# Aux_Board_V7_0.net
KiCad netlist of a schematic drawn in EAGLE
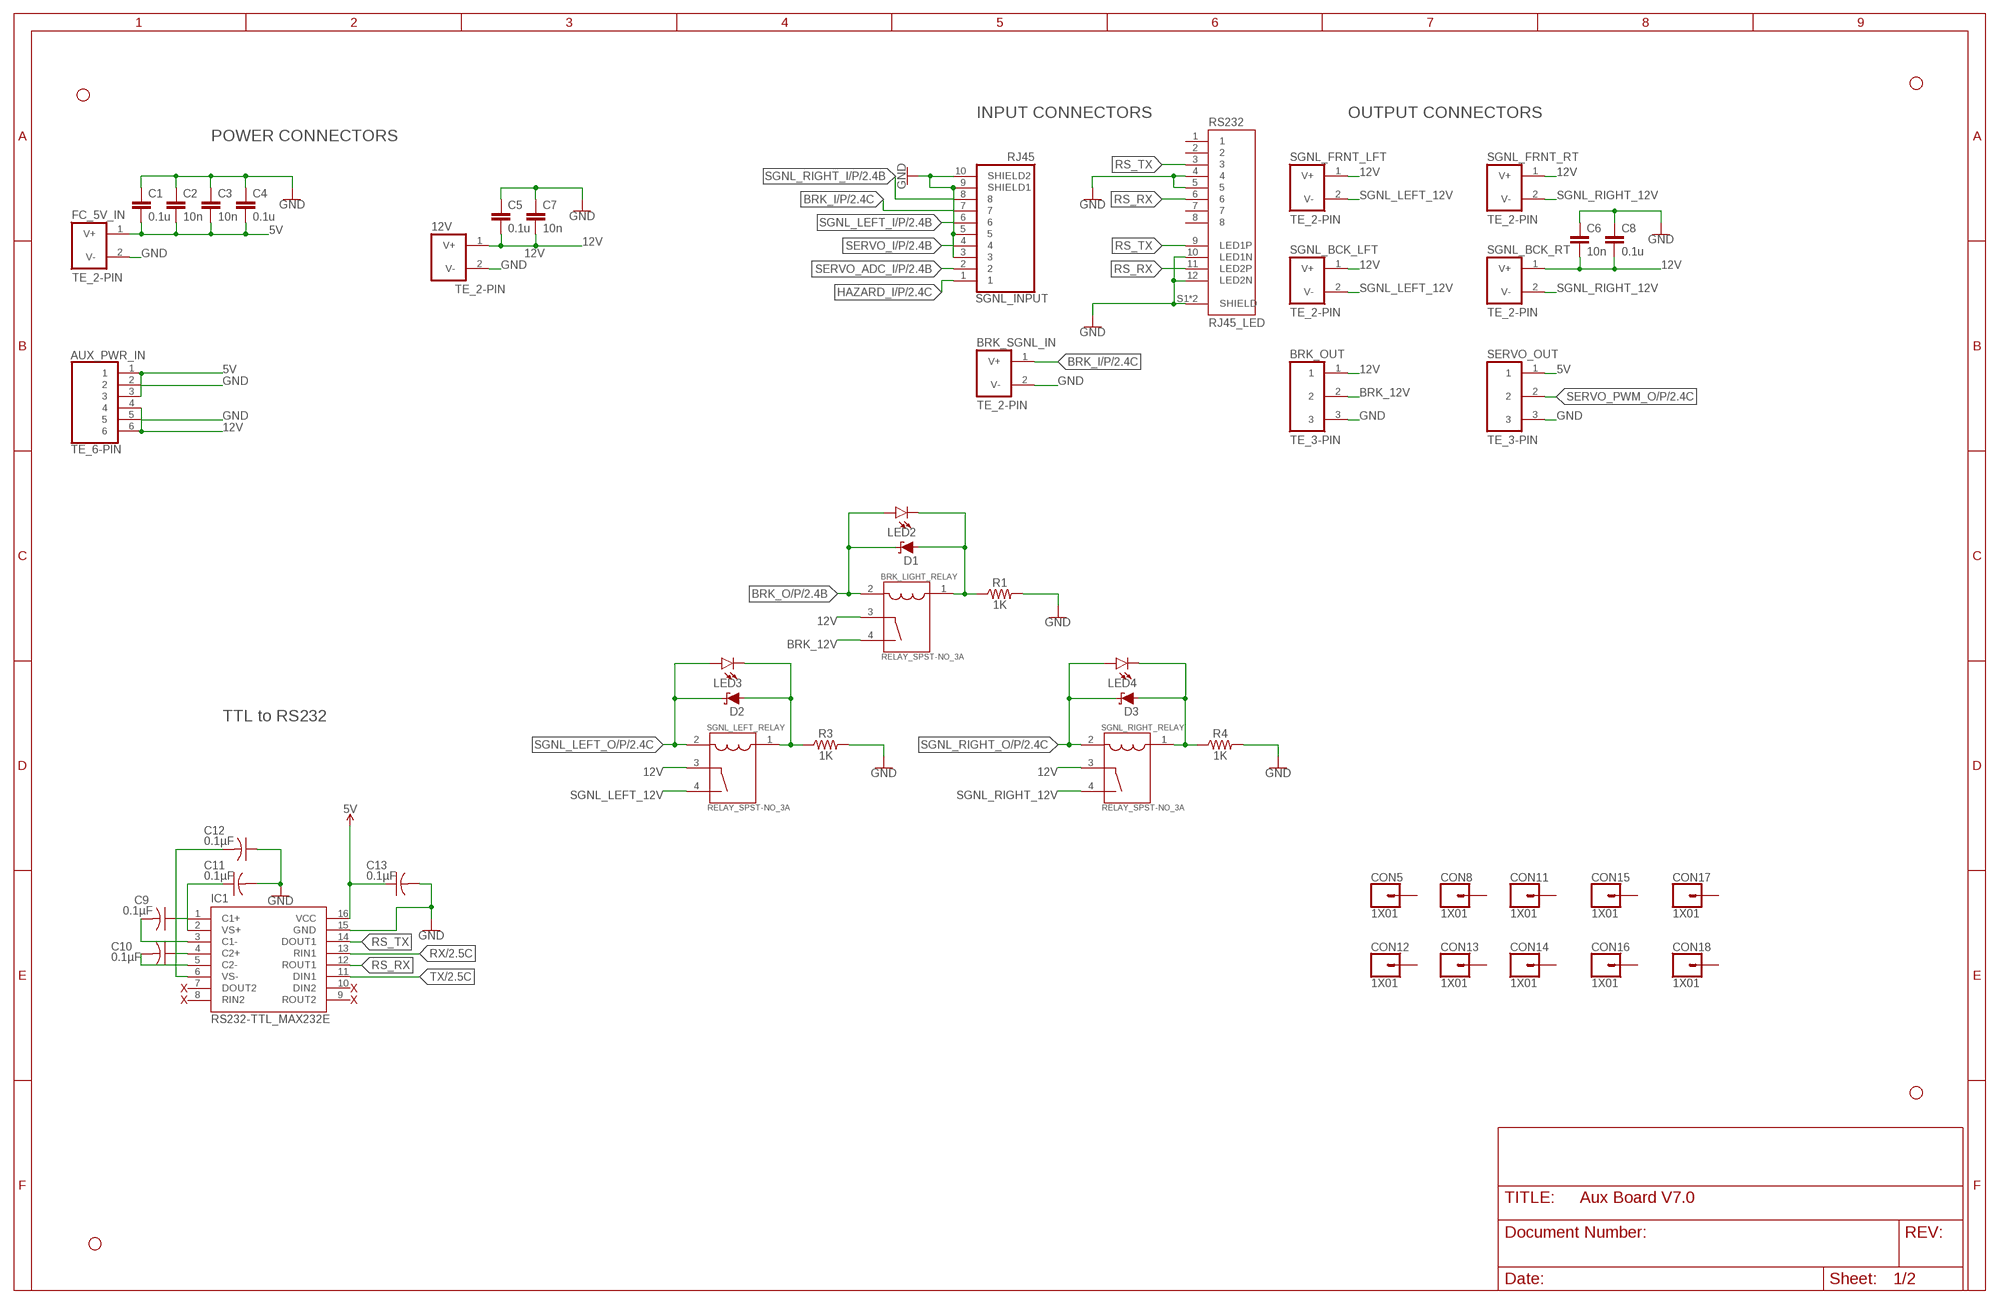
[diagram p0: schematic, sheet 1]
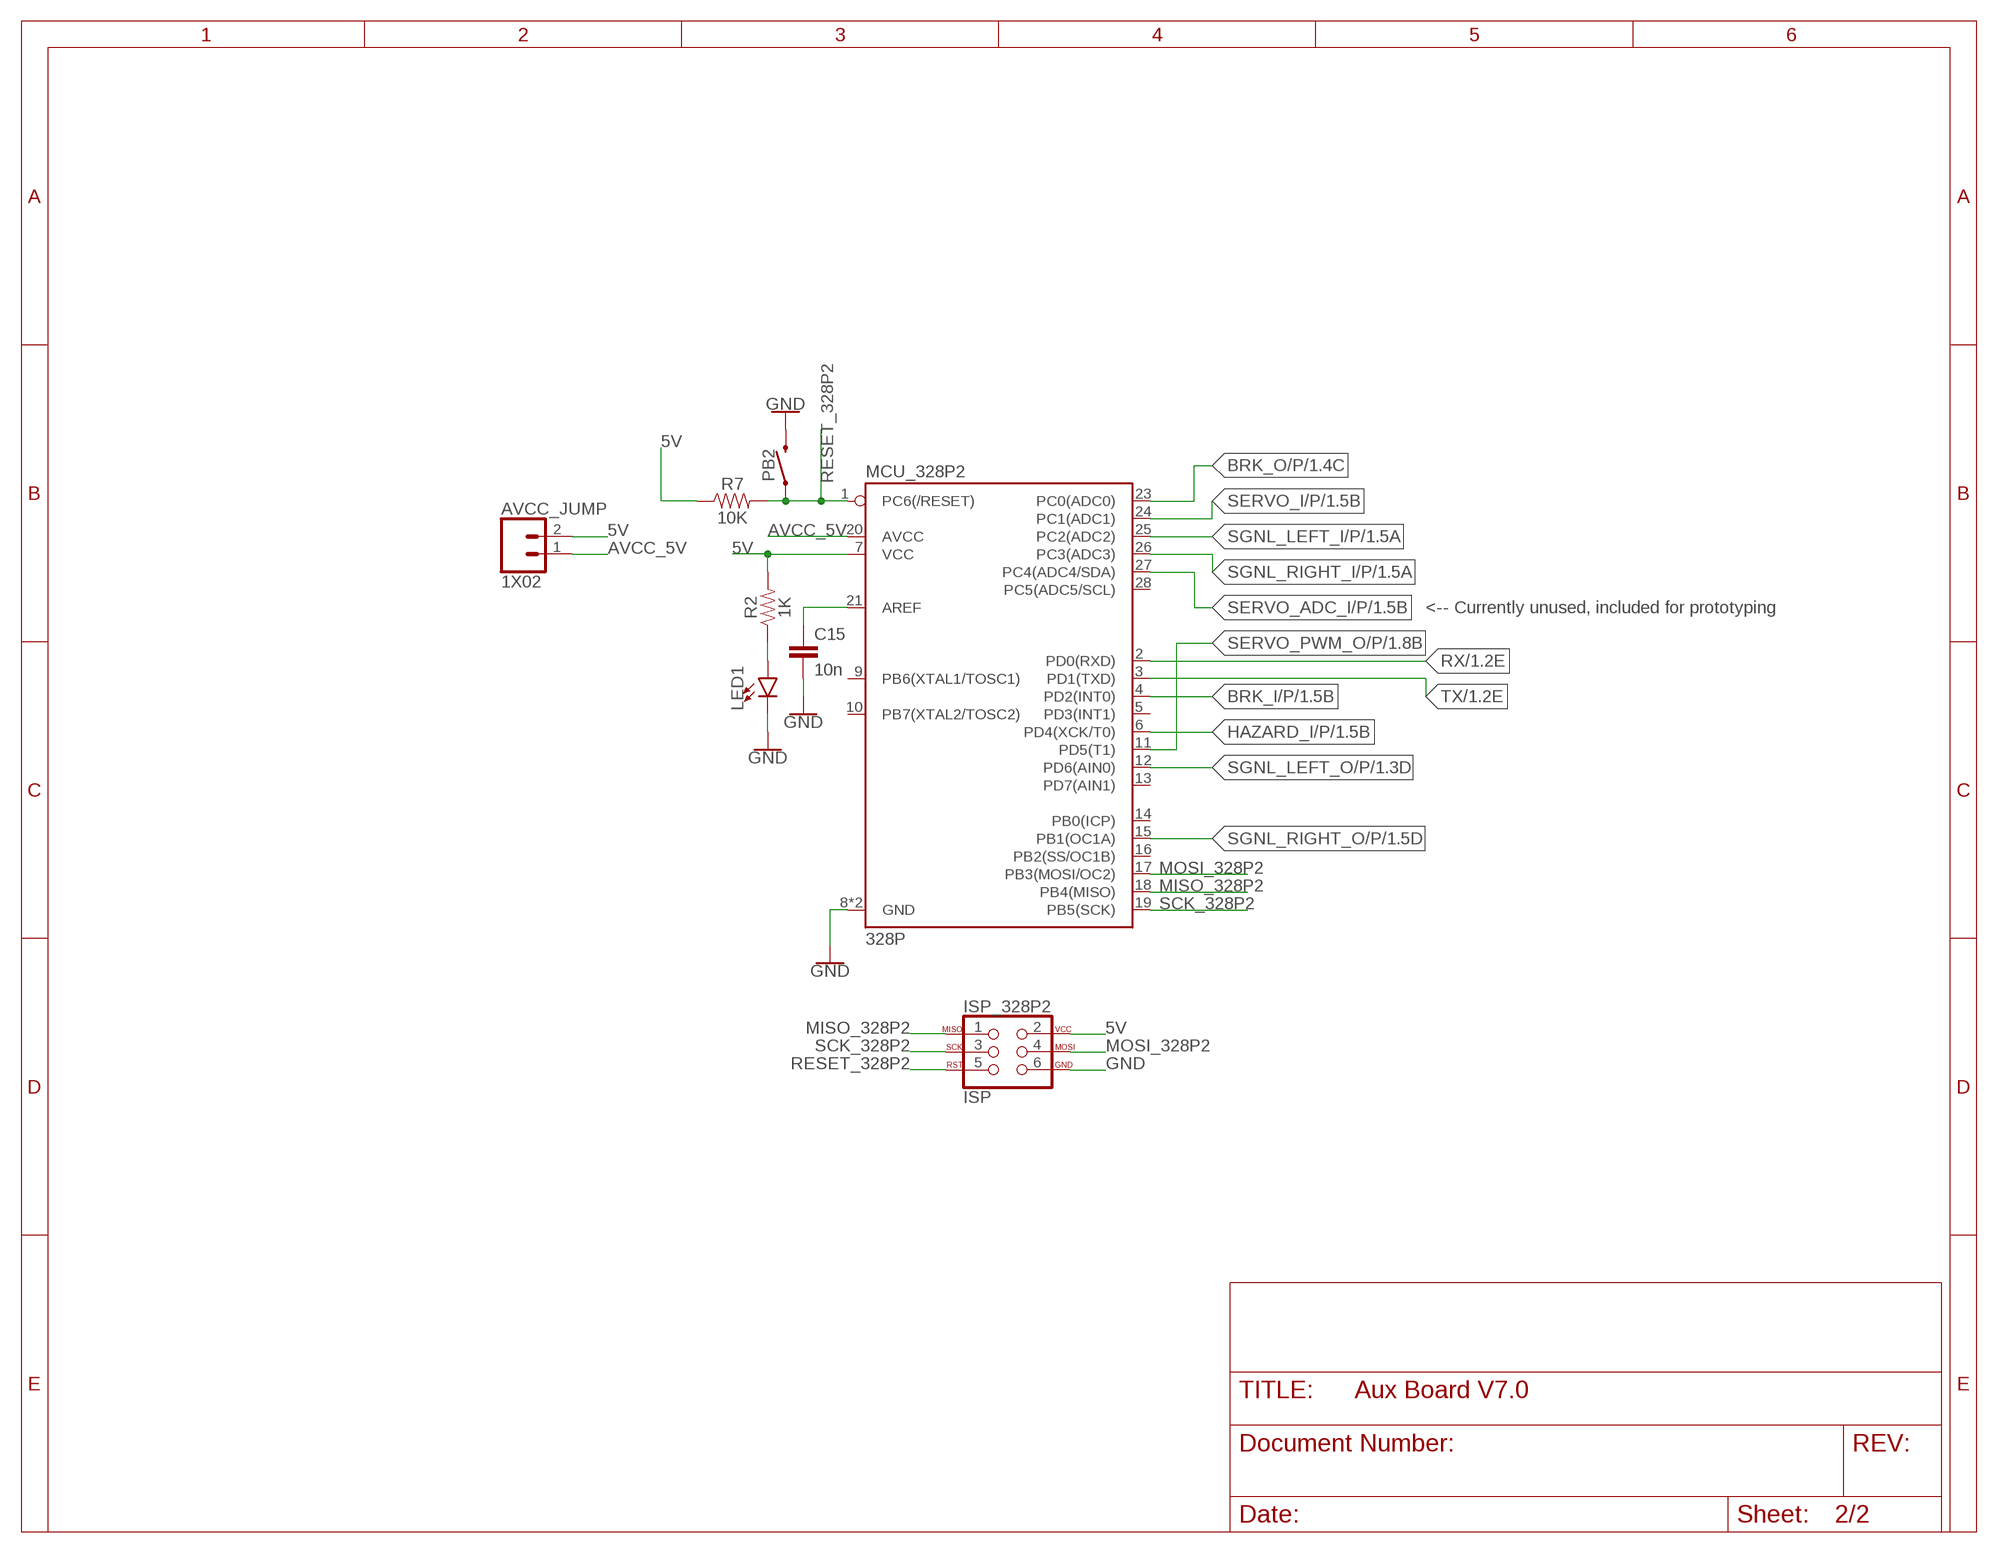
[diagram p1: schematic, sheet 2]

(export (version "E")
  (design (tool "Eeschema 10.0.6"))
  (components
    (comp (ref "AVCC_JUMP")
      (value "1X02")
      (footprint "eagle-import:1X02")
      (libsource (lib "eagle-import") (part "1X02"))
    )
    (comp (ref "C15")
      (value "10n")
      (footprint "eagle-import:0805")
      (libsource (lib "eagle-import") (part "CAPACITOR_0805"))
    )
    (comp (ref "ISP_328P2")
      (value "ISP")
      (footprint "eagle-import:ISP_CONNECTOR")
      (libsource (lib "eagle-import") (part "ISP"))
    )
    (comp (ref "LED1")
      (value "LED_0805")
      (footprint "eagle-import:0805_LED")
      (libsource (lib "eagle-import") (part "LED_0805"))
    )
    (comp (ref "MCU_328P2")
      (value "328P")
      (footprint "eagle-import:DIP28")
      (libsource (lib "eagle-import") (part "ATMEGA328P_DIP28"))
    )
    (comp (ref "PB2")
      (value "PUSHBUTTON")
      (footprint "eagle-import:PUSHBUTTON")
      (libsource (lib "eagle-import") (part "PUSHBUTTON"))
    )
    (comp (ref "R2")
      (value "1K")
      (footprint "eagle-import:0805")
      (libsource (lib "eagle-import") (part "RESISTOR_0805"))
    )
    (comp (ref "R7")
      (value "10K")
      (footprint "eagle-import:0805")
      (libsource (lib "eagle-import") (part "RESISTOR_0805"))
    )
    (comp (ref "12V")
      (value "TE_2-PIN")
      (footprint "eagle-import:TE_2-PIN")
      (libsource (lib "eagle-import") (part "TE_2-PIN"))
    )
    (comp (ref "AUX_PWR_IN")
      (value "TE_6-PIN")
      (footprint "eagle-import:TE_6-PIN")
      (libsource (lib "eagle-import") (part "TE_6-PIN"))
    )
    (comp (ref "BRK_LIGHT_RELAY")
      (value "RELAY_SPST-NO_3A")
      (footprint "eagle-import:TE_1-1721081-2")
      (fields (field (name "COMMENT") "1-1721081-2") (field (name "MF") "TE Connectivity"))
      (libsource (lib "eagle-import") (part "RELAY_SPST-NO_3A"))
    )
    (comp (ref "BRK_OUT")
      (value "TE_3-PIN")
      (footprint "eagle-import:TE_3-PIN")
      (libsource (lib "eagle-import") (part "TE_3-PIN"))
    )
    (comp (ref "BRK_SGNL_IN")
      (value "TE_2-PIN")
      (footprint "eagle-import:TE_2-PIN")
      (libsource (lib "eagle-import") (part "TE_2-PIN"))
    )
    (comp (ref "C1")
      (value "0.1u")
      (footprint "eagle-import:0805")
      (libsource (lib "eagle-import") (part "CAPACITOR_0805"))
    )
    (comp (ref "C2")
      (value "10n")
      (footprint "eagle-import:0805")
      (libsource (lib "eagle-import") (part "CAPACITOR_0805"))
    )
    (comp (ref "C3")
      (value "10n")
      (footprint "eagle-import:0805")
      (libsource (lib "eagle-import") (part "CAPACITOR_0805"))
    )
    (comp (ref "C4")
      (value "0.1u")
      (footprint "eagle-import:0805")
      (libsource (lib "eagle-import") (part "CAPACITOR_0805"))
    )
    (comp (ref "C5")
      (value "0.1u")
      (footprint "eagle-import:0805")
      (libsource (lib "eagle-import") (part "CAPACITOR_0805"))
    )
    (comp (ref "C6")
      (value "10n")
      (footprint "eagle-import:0805")
      (libsource (lib "eagle-import") (part "CAPACITOR_0805"))
    )
    (comp (ref "C7")
      (value "10n")
      (footprint "eagle-import:0805")
      (libsource (lib "eagle-import") (part "CAPACITOR_0805"))
    )
    (comp (ref "C8")
      (value "0.1u")
      (footprint "eagle-import:0805")
      (libsource (lib "eagle-import") (part "CAPACITOR_0805"))
    )
    (comp (ref "C9")
      (value "0.1µF")
      (footprint "eagle-import:C0805")
      (libsource (lib "eagle-import") (part "C-USC0805"))
    )
    (comp (ref "C10")
      (value "0.1µF")
      (footprint "eagle-import:C0805")
      (libsource (lib "eagle-import") (part "C-USC0805"))
    )
    (comp (ref "C11")
      (value "0.1µF")
      (footprint "eagle-import:C0805")
      (libsource (lib "eagle-import") (part "C-USC0805"))
    )
    (comp (ref "C12")
      (value "0.1µF")
      (footprint "eagle-import:C0805")
      (libsource (lib "eagle-import") (part "C-USC0805"))
    )
    (comp (ref "C13")
      (value "0.1µF")
      (footprint "eagle-import:C0805")
      (libsource (lib "eagle-import") (part "C-USC0805"))
    )
    (comp (ref "CON5")
      (value "1X01")
      (footprint "eagle-import:1X01")
      (libsource (lib "eagle-import") (part "1X01"))
    )
    (comp (ref "CON8")
      (value "1X01")
      (footprint "eagle-import:1X01")
      (libsource (lib "eagle-import") (part "1X01"))
    )
    (comp (ref "CON11")
      (value "1X01")
      (footprint "eagle-import:1X01")
      (libsource (lib "eagle-import") (part "1X01"))
    )
    (comp (ref "CON12")
      (value "1X01")
      (footprint "eagle-import:1X01")
      (libsource (lib "eagle-import") (part "1X01"))
    )
    (comp (ref "CON13")
      (value "1X01")
      (footprint "eagle-import:1X01")
      (libsource (lib "eagle-import") (part "1X01"))
    )
    (comp (ref "CON14")
      (value "1X01")
      (footprint "eagle-import:1X01")
      (libsource (lib "eagle-import") (part "1X01"))
    )
    (comp (ref "CON15")
      (value "1X01")
      (footprint "eagle-import:1X01")
      (libsource (lib "eagle-import") (part "1X01"))
    )
    (comp (ref "CON16")
      (value "1X01")
      (footprint "eagle-import:1X01")
      (libsource (lib "eagle-import") (part "1X01"))
    )
    (comp (ref "CON17")
      (value "1X01")
      (footprint "eagle-import:1X01")
      (libsource (lib "eagle-import") (part "1X01"))
    )
    (comp (ref "CON18")
      (value "1X01")
      (footprint "eagle-import:1X01")
      (libsource (lib "eagle-import") (part "1X01"))
    )
    (comp (ref "D1")
      (value "DIODE_SCHOTTKY_DO-214AA")
      (footprint "eagle-import:DO214AA")
      (libsource (lib "eagle-import") (part "DIODE_SCHOTTKY_DO-214AA"))
    )
    (comp (ref "D2")
      (value "DIODE_SCHOTTKY_DO-214AA")
      (footprint "eagle-import:DO214AA")
      (libsource (lib "eagle-import") (part "DIODE_SCHOTTKY_DO-214AA"))
    )
    (comp (ref "D3")
      (value "DIODE_SCHOTTKY_DO-214AA")
      (footprint "eagle-import:DO214AA")
      (libsource (lib "eagle-import") (part "DIODE_SCHOTTKY_DO-214AA"))
    )
    (comp (ref "FC_5V_IN")
      (value "TE_2-PIN")
      (footprint "eagle-import:TE_2-PIN")
      (libsource (lib "eagle-import") (part "TE_2-PIN"))
    )
    (comp (ref "H1")
      (value "STAND-OFF")
      (footprint "eagle-import:STAND-OFF")
      (libsource (lib "eagle-import") (part "STAND-OFF"))
    )
    (comp (ref "H2")
      (value "STAND-OFF")
      (footprint "eagle-import:STAND-OFF")
      (libsource (lib "eagle-import") (part "STAND-OFF"))
    )
    (comp (ref "H3")
      (value "STAND-OFF")
      (footprint "eagle-import:STAND-OFF")
      (libsource (lib "eagle-import") (part "STAND-OFF"))
    )
    (comp (ref "H4")
      (value "STAND-OFF")
      (footprint "eagle-import:STAND-OFF")
      (libsource (lib "eagle-import") (part "STAND-OFF"))
    )
    (comp (ref "IC1")
      (value "RS232-TTL_MAX232E")
      (footprint "eagle-import:DIP16")
      (libsource (lib "eagle-import") (part "RS232-TTL_MAX232E"))
    )
    (comp (ref "LED2")
      (value "LED_0805")
      (footprint "eagle-import:0805_LED")
      (libsource (lib "eagle-import") (part "LED_0805"))
    )
    (comp (ref "LED3")
      (value "LED_0805")
      (footprint "eagle-import:0805_LED")
      (libsource (lib "eagle-import") (part "LED_0805"))
    )
    (comp (ref "LED4")
      (value "LED_0805")
      (footprint "eagle-import:0805_LED")
      (libsource (lib "eagle-import") (part "LED_0805"))
    )
    (comp (ref "R1")
      (value "1K")
      (footprint "eagle-import:0805")
      (libsource (lib "eagle-import") (part "RESISTOR_0805"))
    )
    (comp (ref "R3")
      (value "1K")
      (footprint "eagle-import:0805")
      (libsource (lib "eagle-import") (part "RESISTOR_0805"))
    )
    (comp (ref "R4")
      (value "1K")
      (footprint "eagle-import:0805")
      (libsource (lib "eagle-import") (part "RESISTOR_0805"))
    )
    (comp (ref "RS232")
      (value "RJ45_LED")
      (footprint "eagle-import:RJ45_LED")
      (fields (field (name "COMMENT") "6116173-4") (field (name "MF") "TE Connectivity"))
      (libsource (lib "eagle-import") (part "RJ45_LED"))
    )
    (comp (ref "SERVO_OUT")
      (value "TE_3-PIN")
      (footprint "eagle-import:TE_3-PIN")
      (libsource (lib "eagle-import") (part "TE_3-PIN"))
    )
    (comp (ref "SGNL_BCK_LFT")
      (value "TE_2-PIN")
      (footprint "eagle-import:TE_2-PIN")
      (libsource (lib "eagle-import") (part "TE_2-PIN"))
    )
    (comp (ref "SGNL_BCK_RT")
      (value "TE_2-PIN")
      (footprint "eagle-import:TE_2-PIN")
      (libsource (lib "eagle-import") (part "TE_2-PIN"))
    )
    (comp (ref "SGNL_FRNT_LFT")
      (value "TE_2-PIN")
      (footprint "eagle-import:TE_2-PIN")
      (libsource (lib "eagle-import") (part "TE_2-PIN"))
    )
    (comp (ref "SGNL_FRNT_RT")
      (value "TE_2-PIN")
      (footprint "eagle-import:TE_2-PIN")
      (libsource (lib "eagle-import") (part "TE_2-PIN"))
    )
    (comp (ref "SGNL_INPUT")
      (value "RJ45")
      (footprint "eagle-import:RJ45")
      (libsource (lib "eagle-import") (part "RJ45"))
    )
    (comp (ref "SGNL_LEFT_RELAY")
      (value "RELAY_SPST-NO_3A")
      (footprint "eagle-import:TE_1-1721081-2")
      (fields (field (name "COMMENT") "1-1721081-2") (field (name "MF") "TE Connectivity"))
      (libsource (lib "eagle-import") (part "RELAY_SPST-NO_3A"))
    )
    (comp (ref "SGNL_RIGHT_RELAY")
      (value "RELAY_SPST-NO_3A")
      (footprint "eagle-import:TE_1-1721081-2")
      (fields (field (name "COMMENT") "1-1721081-2") (field (name "MF") "TE Connectivity"))
      (libsource (lib "eagle-import") (part "RELAY_SPST-NO_3A"))
    )
  )
  (nets
    (net (code "1") (name "5V") (class "Default")
      (node (ref "AUX_PWR_IN") (pin "1") (pinfunction "1_1") (pintype "passive"))
      (node (ref "AUX_PWR_IN") (pin "3") (pinfunction "3_3") (pintype "passive"))
      (node (ref "AVCC_JUMP") (pin "2") (pinfunction "2_2") (pintype "passive"))
      (node (ref "C1") (pin "2") (pinfunction "2_2") (pintype "passive"))
      (node (ref "C13") (pin "1") (pinfunction "1_1") (pintype "passive"))
      (node (ref "C2") (pin "2") (pinfunction "2_2") (pintype "passive"))
      (node (ref "C3") (pin "2") (pinfunction "2_2") (pintype "passive"))
      (node (ref "C4") (pin "2") (pinfunction "2_2") (pintype "passive"))
      (node (ref "FC_5V_IN") (pin "1") (pinfunction "V+_1") (pintype "passive"))
      (node (ref "IC1") (pin "16") (pinfunction "VCC_16") (pintype "bidirectional"))
      (node (ref "ISP_328P2") (pin "2") (pinfunction "2_2") (pintype "passive"))
      (node (ref "MCU_328P2") (pin "7") (pinfunction "VCC_7") (pintype "bidirectional"))
      (node (ref "R2") (pin "2") (pinfunction "2_2") (pintype "passive"))
      (node (ref "R7") (pin "1") (pinfunction "1_1") (pintype "passive"))
      (node (ref "SERVO_OUT") (pin "1") (pinfunction "1_1") (pintype "passive"))
    )
    (net (code "2") (name "12V") (class "Default")
      (node (ref "12V") (pin "1") (pinfunction "V+_1") (pintype "passive"))
      (node (ref "AUX_PWR_IN") (pin "4") (pinfunction "4_4") (pintype "passive"))
      (node (ref "AUX_PWR_IN") (pin "6") (pinfunction "6_6") (pintype "passive"))
      (node (ref "BRK_LIGHT_RELAY") (pin "3") (pinfunction "3_3") (pintype "passive"))
      (node (ref "BRK_OUT") (pin "1") (pinfunction "1_1") (pintype "passive"))
      (node (ref "C5") (pin "2") (pinfunction "2_2") (pintype "passive"))
      (node (ref "C6") (pin "2") (pinfunction "2_2") (pintype "passive"))
      (node (ref "C7") (pin "2") (pinfunction "2_2") (pintype "passive"))
      (node (ref "C8") (pin "2") (pinfunction "2_2") (pintype "passive"))
      (node (ref "SGNL_BCK_LFT") (pin "1") (pinfunction "V+_1") (pintype "passive"))
      (node (ref "SGNL_BCK_RT") (pin "1") (pinfunction "V+_1") (pintype "passive"))
      (node (ref "SGNL_FRNT_LFT") (pin "1") (pinfunction "V+_1") (pintype "passive"))
      (node (ref "SGNL_FRNT_RT") (pin "1") (pinfunction "V+_1") (pintype "passive"))
      (node (ref "SGNL_LEFT_RELAY") (pin "3") (pinfunction "3_3") (pintype "passive"))
      (node (ref "SGNL_RIGHT_RELAY") (pin "3") (pinfunction "3_3") (pintype "passive"))
    )
    (net (code "3") (name "AVCC_5V") (class "Default")
      (node (ref "AVCC_JUMP") (pin "1") (pinfunction "1_1") (pintype "passive"))
      (node (ref "MCU_328P2") (pin "20") (pinfunction "AVCC_20") (pintype "bidirectional"))
    )
    (net (code "4") (name "BRK_12V") (class "Default")
      (node (ref "BRK_LIGHT_RELAY") (pin "4") (pinfunction "4_4") (pintype "passive"))
      (node (ref "BRK_OUT") (pin "2") (pinfunction "2_2") (pintype "passive"))
    )
    (net (code "5") (name "BRK_I{slash}P") (class "Default")
      (node (ref "BRK_SGNL_IN") (pin "1") (pinfunction "V+_1") (pintype "passive"))
      (node (ref "MCU_328P2") (pin "4") (pinfunction "PD2(INT0)_4") (pintype "bidirectional"))
      (node (ref "SGNL_INPUT") (pin "7") (pinfunction "7_7") (pintype "passive"))
    )
    (net (code "6") (name "BRK_O{slash}P") (class "Default")
      (node (ref "BRK_LIGHT_RELAY") (pin "2") (pinfunction "2_2") (pintype "passive"))
      (node (ref "D1") (pin "C") (pinfunction "C_C") (pintype "passive"))
      (node (ref "LED2") (pin "1") (pinfunction "A_1") (pintype "passive"))
      (node (ref "MCU_328P2") (pin "23") (pinfunction "PC0(ADC0)_23") (pintype "bidirectional"))
    )
    (net (code "7") (name "GND") (class "Default")
      (node (ref "12V") (pin "2") (pinfunction "V-_2") (pintype "passive"))
      (node (ref "AUX_PWR_IN") (pin "2") (pinfunction "2_2") (pintype "passive"))
      (node (ref "AUX_PWR_IN") (pin "5") (pinfunction "5_5") (pintype "passive"))
      (node (ref "BRK_OUT") (pin "3") (pinfunction "3_3") (pintype "passive"))
      (node (ref "BRK_SGNL_IN") (pin "2") (pinfunction "V-_2") (pintype "passive"))
      (node (ref "C1") (pin "1") (pinfunction "1_1") (pintype "passive"))
      (node (ref "C11") (pin "2") (pinfunction "2_2") (pintype "passive"))
      (node (ref "C12") (pin "1") (pinfunction "1_1") (pintype "passive"))
      (node (ref "C13") (pin "2") (pinfunction "2_2") (pintype "passive"))
      (node (ref "C15") (pin "2") (pinfunction "2_2") (pintype "passive"))
      (node (ref "C2") (pin "1") (pinfunction "1_1") (pintype "passive"))
      (node (ref "C3") (pin "1") (pinfunction "1_1") (pintype "passive"))
      (node (ref "C4") (pin "1") (pinfunction "1_1") (pintype "passive"))
      (node (ref "C5") (pin "1") (pinfunction "1_1") (pintype "passive"))
      (node (ref "C6") (pin "1") (pinfunction "1_1") (pintype "passive"))
      (node (ref "C7") (pin "1") (pinfunction "1_1") (pintype "passive"))
      (node (ref "C8") (pin "1") (pinfunction "1_1") (pintype "passive"))
      (node (ref "FC_5V_IN") (pin "2") (pinfunction "V-_2") (pintype "passive"))
      (node (ref "IC1") (pin "15") (pinfunction "GND_15") (pintype "bidirectional"))
      (node (ref "ISP_328P2") (pin "6") (pinfunction "6_6") (pintype "passive"))
      (node (ref "LED1") (pin "2") (pinfunction "C_2") (pintype "passive"))
      (node (ref "MCU_328P2") (pin "22") (pinfunction "GND_22") (pintype "bidirectional"))
      (node (ref "MCU_328P2") (pin "8") (pinfunction "GND_8") (pintype "bidirectional"))
      (node (ref "PB2") (pin "3") (pinfunction "2_3") (pintype "passive"))
      (node (ref "PB2") (pin "4") (pinfunction "2_4") (pintype "passive"))
      (node (ref "R1") (pin "2") (pinfunction "2_2") (pintype "passive"))
      (node (ref "R3") (pin "2") (pinfunction "2_2") (pintype "passive"))
      (node (ref "R4") (pin "2") (pinfunction "2_2") (pintype "passive"))
      (node (ref "RS232") (pin "10") (pinfunction "LED1N_10") (pintype "passive"))
      (node (ref "RS232") (pin "12") (pinfunction "LED2N_12") (pintype "passive"))
      (node (ref "RS232") (pin "4") (pinfunction "4_4") (pintype "passive"))
      (node (ref "RS232") (pin "5") (pinfunction "5_5") (pintype "passive"))
      (node (ref "RS232") (pin "S1") (pinfunction "SHIELD_S1") (pintype "passive"))
      (node (ref "RS232") (pin "S2") (pinfunction "SHIELD_S2") (pintype "passive"))
      (node (ref "SERVO_OUT") (pin "3") (pinfunction "3_3") (pintype "passive"))
      (node (ref "SGNL_INPUT") (pin "10") (pinfunction "SHIELD2_10") (pintype "passive"))
      (node (ref "SGNL_INPUT") (pin "3") (pinfunction "3_3") (pintype "passive"))
      (node (ref "SGNL_INPUT") (pin "5") (pinfunction "5_5") (pintype "passive"))
      (node (ref "SGNL_INPUT") (pin "9") (pinfunction "SHIELD1_9") (pintype "passive"))
    )
    (net (code "8") (name "HAZARD_I{slash}P") (class "Default")
      (node (ref "MCU_328P2") (pin "6") (pinfunction "PD4(XCK/T0)_6") (pintype "bidirectional"))
      (node (ref "SGNL_INPUT") (pin "1") (pinfunction "1_1") (pintype "passive"))
    )
    (net (code "9") (name "MISO_328P2") (class "Default")
      (node (ref "ISP_328P2") (pin "1") (pinfunction "1_1") (pintype "passive"))
      (node (ref "MCU_328P2") (pin "18") (pinfunction "PB4(MISO)_18") (pintype "bidirectional"))
    )
    (net (code "10") (name "MOSI_328P2") (class "Default")
      (node (ref "ISP_328P2") (pin "4") (pinfunction "4_4") (pintype "passive"))
      (node (ref "MCU_328P2") (pin "17") (pinfunction "PB3(MOSI/OC2)_17") (pintype "bidirectional"))
    )
    (net (code "11") (name "Net-(IC1-C1+)") (class "Default")
      (node (ref "C9") (pin "1") (pinfunction "1_1") (pintype "passive"))
      (node (ref "IC1") (pin "1") (pinfunction "C1+_1") (pintype "bidirectional"))
    )
    (net (code "12") (name "Net-(IC1-C1-)") (class "Default")
      (node (ref "C9") (pin "2") (pinfunction "2_2") (pintype "passive"))
      (node (ref "IC1") (pin "3") (pinfunction "C1-_3") (pintype "bidirectional"))
    )
    (net (code "13") (name "Net-(IC1-C2+)") (class "Default")
      (node (ref "C10") (pin "1") (pinfunction "1_1") (pintype "passive"))
      (node (ref "IC1") (pin "4") (pinfunction "C2+_4") (pintype "bidirectional"))
    )
    (net (code "14") (name "Net-(IC1-C2-)") (class "Default")
      (node (ref "C10") (pin "2") (pinfunction "2_2") (pintype "passive"))
      (node (ref "IC1") (pin "5") (pinfunction "C2-_5") (pintype "bidirectional"))
    )
    (net (code "15") (name "Net-(IC1-VS+)") (class "Default")
      (node (ref "C11") (pin "1") (pinfunction "1_1") (pintype "passive"))
      (node (ref "IC1") (pin "2") (pinfunction "VS+_2") (pintype "bidirectional"))
    )
    (net (code "16") (name "Net-(IC1-VS-)") (class "Default")
      (node (ref "C12") (pin "2") (pinfunction "2_2") (pintype "passive"))
      (node (ref "IC1") (pin "6") (pinfunction "VS-_6") (pintype "bidirectional"))
    )
    (net (code "17") (name "Net-(LED1-A)") (class "Default")
      (node (ref "LED1") (pin "1") (pinfunction "A_1") (pintype "passive"))
      (node (ref "R2") (pin "1") (pinfunction "1_1") (pintype "passive"))
    )
    (net (code "18") (name "Net-(LED2-C)") (class "Default")
      (node (ref "BRK_LIGHT_RELAY") (pin "1") (pinfunction "1_1") (pintype "passive"))
      (node (ref "D1") (pin "A") (pinfunction "A_A") (pintype "passive"))
      (node (ref "LED2") (pin "2") (pinfunction "C_2") (pintype "passive"))
      (node (ref "R1") (pin "1") (pinfunction "1_1") (pintype "passive"))
    )
    (net (code "19") (name "Net-(LED3-C)") (class "Default")
      (node (ref "D2") (pin "A") (pinfunction "A_A") (pintype "passive"))
      (node (ref "LED3") (pin "2") (pinfunction "C_2") (pintype "passive"))
      (node (ref "R3") (pin "1") (pinfunction "1_1") (pintype "passive"))
      (node (ref "SGNL_LEFT_RELAY") (pin "1") (pinfunction "1_1") (pintype "passive"))
    )
    (net (code "20") (name "Net-(LED4-C)") (class "Default")
      (node (ref "D3") (pin "A") (pinfunction "A_A") (pintype "passive"))
      (node (ref "LED4") (pin "2") (pinfunction "C_2") (pintype "passive"))
      (node (ref "R4") (pin "1") (pinfunction "1_1") (pintype "passive"))
      (node (ref "SGNL_RIGHT_RELAY") (pin "1") (pinfunction "1_1") (pintype "passive"))
    )
    (net (code "21") (name "Net-(MCU_328P2-AREF)") (class "Default")
      (node (ref "C15") (pin "1") (pinfunction "1_1") (pintype "passive"))
      (node (ref "MCU_328P2") (pin "21") (pinfunction "AREF_21") (pintype "bidirectional"))
    )
    (net (code "22") (name "RESET_328P2") (class "Default")
      (node (ref "ISP_328P2") (pin "5") (pinfunction "5_5") (pintype "passive"))
      (node (ref "MCU_328P2") (pin "1") (pinfunction "PC6(/RESET)_1") (pintype "bidirectional"))
      (node (ref "PB2") (pin "1") (pinfunction "1_1") (pintype "passive"))
      (node (ref "PB2") (pin "2") (pinfunction "1_2") (pintype "passive"))
      (node (ref "R7") (pin "2") (pinfunction "2_2") (pintype "passive"))
    )
    (net (code "23") (name "RS_RX") (class "Default")
      (node (ref "IC1") (pin "12") (pinfunction "ROUT1_12") (pintype "bidirectional"))
      (node (ref "RS232") (pin "11") (pinfunction "LED2P_11") (pintype "passive"))
      (node (ref "RS232") (pin "6") (pinfunction "6_6") (pintype "passive"))
    )
    (net (code "24") (name "RS_TX") (class "Default")
      (node (ref "IC1") (pin "14") (pinfunction "DOUT1_14") (pintype "bidirectional"))
      (node (ref "RS232") (pin "3") (pinfunction "3_3") (pintype "passive"))
      (node (ref "RS232") (pin "9") (pinfunction "LED1P_9") (pintype "passive"))
    )
    (net (code "25") (name "RX") (class "Default")
      (node (ref "IC1") (pin "13") (pinfunction "RIN1_13") (pintype "bidirectional"))
      (node (ref "MCU_328P2") (pin "2") (pinfunction "PD0(RXD)_2") (pintype "bidirectional"))
    )
    (net (code "26") (name "SCK_328P2") (class "Default")
      (node (ref "ISP_328P2") (pin "3") (pinfunction "3_3") (pintype "passive"))
      (node (ref "MCU_328P2") (pin "19") (pinfunction "PB5(SCK)_19") (pintype "bidirectional"))
    )
    (net (code "27") (name "SERVO_ADC_I{slash}P") (class "Default")
      (node (ref "MCU_328P2") (pin "27") (pinfunction "PC4(ADC4/SDA)_27") (pintype "bidirectional"))
      (node (ref "SGNL_INPUT") (pin "2") (pinfunction "2_2") (pintype "passive"))
    )
    (net (code "28") (name "SERVO_I{slash}P") (class "Default")
      (node (ref "MCU_328P2") (pin "24") (pinfunction "PC1(ADC1)_24") (pintype "bidirectional"))
      (node (ref "SGNL_INPUT") (pin "4") (pinfunction "4_4") (pintype "passive"))
    )
    (net (code "29") (name "SERVO_PWM_O{slash}P") (class "Default")
      (node (ref "MCU_328P2") (pin "11") (pinfunction "PD5(T1)_11") (pintype "bidirectional"))
      (node (ref "SERVO_OUT") (pin "2") (pinfunction "2_2") (pintype "passive"))
    )
    (net (code "30") (name "SGNL_LEFT_12V") (class "Default")
      (node (ref "SGNL_BCK_LFT") (pin "2") (pinfunction "V-_2") (pintype "passive"))
      (node (ref "SGNL_FRNT_LFT") (pin "2") (pinfunction "V-_2") (pintype "passive"))
      (node (ref "SGNL_LEFT_RELAY") (pin "4") (pinfunction "4_4") (pintype "passive"))
    )
    (net (code "31") (name "SGNL_LEFT_I{slash}P") (class "Default")
      (node (ref "MCU_328P2") (pin "25") (pinfunction "PC2(ADC2)_25") (pintype "bidirectional"))
      (node (ref "SGNL_INPUT") (pin "6") (pinfunction "6_6") (pintype "passive"))
    )
    (net (code "32") (name "SGNL_LEFT_O{slash}P") (class "Default")
      (node (ref "D2") (pin "C") (pinfunction "C_C") (pintype "passive"))
      (node (ref "LED3") (pin "1") (pinfunction "A_1") (pintype "passive"))
      (node (ref "MCU_328P2") (pin "12") (pinfunction "PD6(AIN0)_12") (pintype "bidirectional"))
      (node (ref "SGNL_LEFT_RELAY") (pin "2") (pinfunction "2_2") (pintype "passive"))
    )
    (net (code "33") (name "SGNL_RIGHT_12V") (class "Default")
      (node (ref "SGNL_BCK_RT") (pin "2") (pinfunction "V-_2") (pintype "passive"))
      (node (ref "SGNL_FRNT_RT") (pin "2") (pinfunction "V-_2") (pintype "passive"))
      (node (ref "SGNL_RIGHT_RELAY") (pin "4") (pinfunction "4_4") (pintype "passive"))
    )
    (net (code "34") (name "SGNL_RIGHT_I{slash}P") (class "Default")
      (node (ref "MCU_328P2") (pin "26") (pinfunction "PC3(ADC3)_26") (pintype "bidirectional"))
      (node (ref "SGNL_INPUT") (pin "8") (pinfunction "8_8") (pintype "passive"))
    )
    (net (code "35") (name "SGNL_RIGHT_O{slash}P") (class "Default")
      (node (ref "D3") (pin "C") (pinfunction "C_C") (pintype "passive"))
      (node (ref "LED4") (pin "1") (pinfunction "A_1") (pintype "passive"))
      (node (ref "MCU_328P2") (pin "15") (pinfunction "PB1(OC1A)_15") (pintype "bidirectional"))
      (node (ref "SGNL_RIGHT_RELAY") (pin "2") (pinfunction "2_2") (pintype "passive"))
    )
    (net (code "36") (name "TX") (class "Default")
      (node (ref "IC1") (pin "11") (pinfunction "DIN1_11") (pintype "bidirectional"))
      (node (ref "MCU_328P2") (pin "3") (pinfunction "PD1(TXD)_3") (pintype "bidirectional"))
    )
    (net (code "37") (name "unconnected-(CON5-Pad1)") (class "Default")
      (node (ref "CON5") (pin "1") (pinfunction "1_1") (pintype "passive"))
    )
    (net (code "38") (name "unconnected-(CON8-Pad1)") (class "Default")
      (node (ref "CON8") (pin "1") (pinfunction "1_1") (pintype "passive"))
    )
    (net (code "39") (name "unconnected-(CON11-Pad1)") (class "Default")
      (node (ref "CON11") (pin "1") (pinfunction "1_1") (pintype "passive"))
    )
    (net (code "40") (name "unconnected-(CON12-Pad1)") (class "Default")
      (node (ref "CON12") (pin "1") (pinfunction "1_1") (pintype "passive"))
    )
    (net (code "41") (name "unconnected-(CON13-Pad1)") (class "Default")
      (node (ref "CON13") (pin "1") (pinfunction "1_1") (pintype "passive"))
    )
    (net (code "42") (name "unconnected-(CON14-Pad1)") (class "Default")
      (node (ref "CON14") (pin "1") (pinfunction "1_1") (pintype "passive"))
    )
    (net (code "43") (name "unconnected-(CON15-Pad1)") (class "Default")
      (node (ref "CON15") (pin "1") (pinfunction "1_1") (pintype "passive"))
    )
    (net (code "44") (name "unconnected-(CON16-Pad1)") (class "Default")
      (node (ref "CON16") (pin "1") (pinfunction "1_1") (pintype "passive"))
    )
    (net (code "45") (name "unconnected-(CON17-Pad1)") (class "Default")
      (node (ref "CON17") (pin "1") (pinfunction "1_1") (pintype "passive"))
    )
    (net (code "46") (name "unconnected-(CON18-Pad1)") (class "Default")
      (node (ref "CON18") (pin "1") (pinfunction "1_1") (pintype "passive"))
    )
    (net (code "47") (name "unconnected-(IC1-DIN2-Pad10)") (class "Default")
      (node (ref "IC1") (pin "10") (pinfunction "DIN2_10") (pintype "bidirectional"))
    )
    (net (code "48") (name "unconnected-(IC1-DOUT2-Pad7)") (class "Default")
      (node (ref "IC1") (pin "7") (pinfunction "DOUT2_7") (pintype "bidirectional"))
    )
    (net (code "49") (name "unconnected-(IC1-RIN2-Pad8)") (class "Default")
      (node (ref "IC1") (pin "8") (pinfunction "RIN2_8") (pintype "bidirectional"))
    )
    (net (code "50") (name "unconnected-(IC1-ROUT2-Pad9)") (class "Default")
      (node (ref "IC1") (pin "9") (pinfunction "ROUT2_9") (pintype "bidirectional"))
    )
    (net (code "51") (name "unconnected-(MCU_328P2-PB0(ICP)-Pad14)") (class "Default")
      (node (ref "MCU_328P2") (pin "14") (pinfunction "PB0(ICP)_14") (pintype "bidirectional"))
    )
    (net (code "52") (name "unconnected-(MCU_328P2-PB2(SS{slash}OC1B)-Pad16)") (class "Default")
      (node (ref "MCU_328P2") (pin "16") (pinfunction "PB2(SS/OC1B)_16") (pintype "bidirectional"))
    )
    (net (code "53") (name "unconnected-(MCU_328P2-PB6(XTAL1{slash}TOSC1)-Pad9)") (class "Default")
      (node (ref "MCU_328P2") (pin "9") (pinfunction "PB6(XTAL1/TOSC1)_9") (pintype "bidirectional"))
    )
    (net (code "54") (name "unconnected-(MCU_328P2-PB7(XTAL2{slash}TOSC2)-Pad10)") (class "Default")
      (node (ref "MCU_328P2") (pin "10") (pinfunction "PB7(XTAL2/TOSC2)_10") (pintype "bidirectional"))
    )
    (net (code "55") (name "unconnected-(MCU_328P2-PC5(ADC5{slash}SCL)-Pad28)") (class "Default")
      (node (ref "MCU_328P2") (pin "28") (pinfunction "PC5(ADC5/SCL)_28") (pintype "bidirectional"))
    )
    (net (code "56") (name "unconnected-(MCU_328P2-PD3(INT1)-Pad5)") (class "Default")
      (node (ref "MCU_328P2") (pin "5") (pinfunction "PD3(INT1)_5") (pintype "bidirectional"))
    )
    (net (code "57") (name "unconnected-(MCU_328P2-PD7(AIN1)-Pad13)") (class "Default")
      (node (ref "MCU_328P2") (pin "13") (pinfunction "PD7(AIN1)_13") (pintype "bidirectional"))
    )
    (net (code "58") (name "unconnected-(RS232-Pad1)") (class "Default")
      (node (ref "RS232") (pin "1") (pinfunction "1_1") (pintype "passive"))
    )
    (net (code "59") (name "unconnected-(RS232-Pad2)") (class "Default")
      (node (ref "RS232") (pin "2") (pinfunction "2_2") (pintype "passive"))
    )
    (net (code "60") (name "unconnected-(RS232-Pad7)") (class "Default")
      (node (ref "RS232") (pin "7") (pinfunction "7_7") (pintype "passive"))
    )
    (net (code "61") (name "unconnected-(RS232-Pad8)") (class "Default")
      (node (ref "RS232") (pin "8") (pinfunction "8_8") (pintype "passive"))
    )
  )
)
